# PSU200A_Ctrl.net
KiCad netlist of a schematic drawn in EAGLE
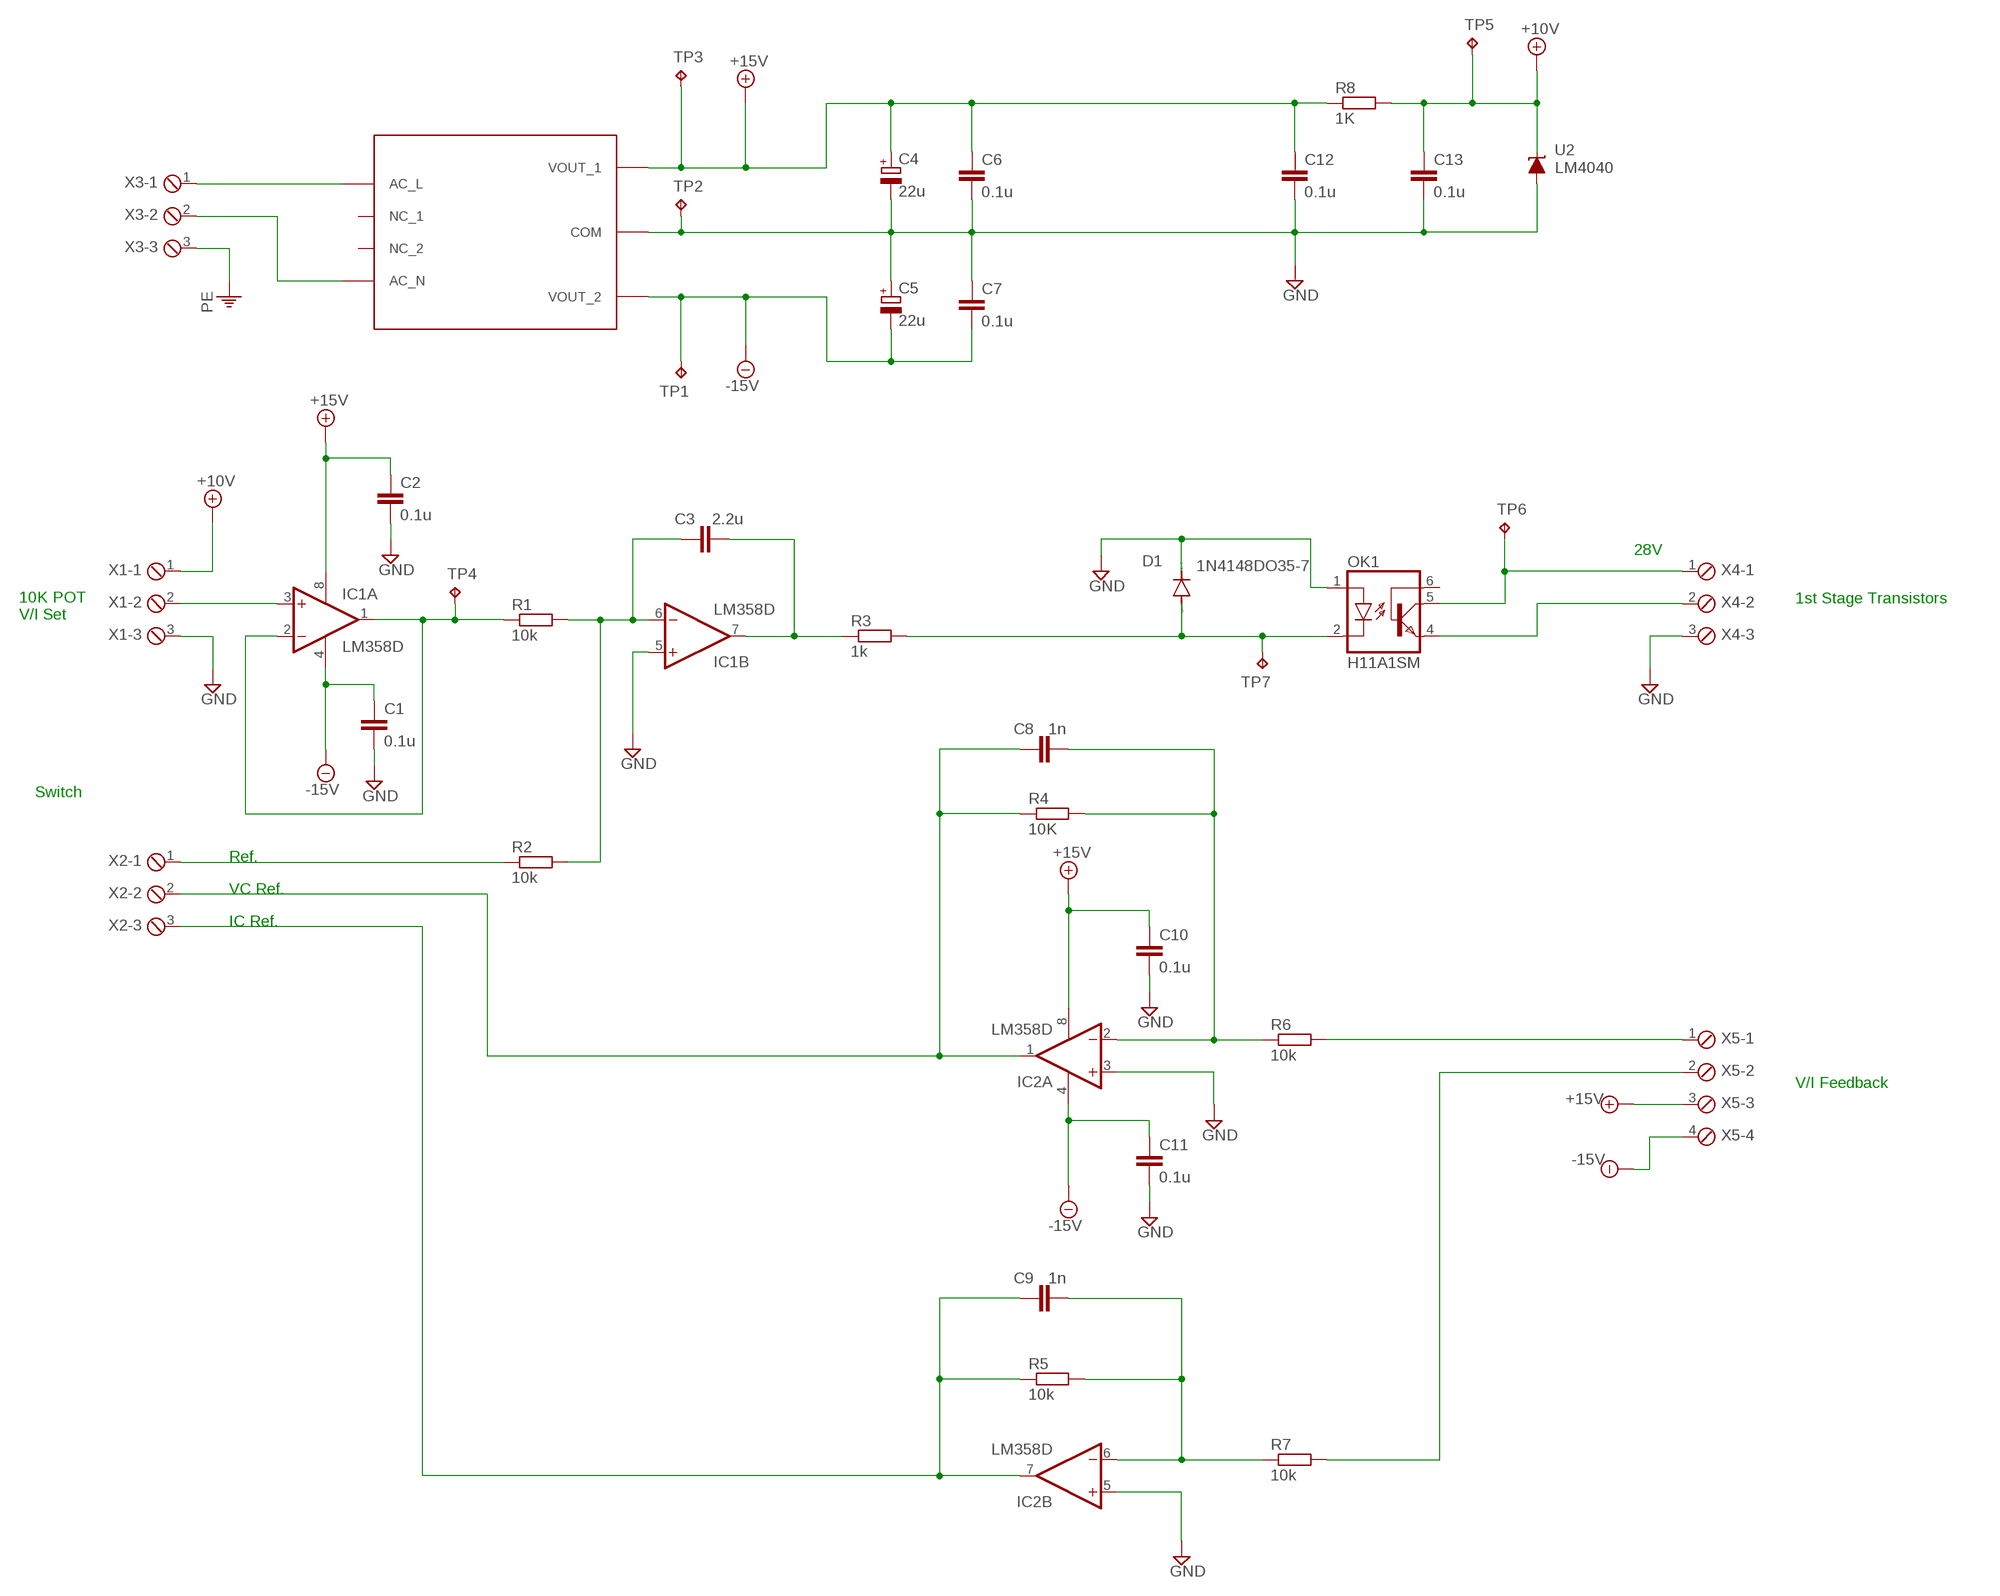
[diagram p0: schematic, sheet 1]

(export (version "E")
  (design (tool "Eeschema 10.0.6"))
  (components
    (comp (ref "C1")
      (value "0.1u")
      (footprint "eagle-import:C1206")
      (libsource (lib "eagle-import") (part "C-EUC1206"))
    )
    (comp (ref "C2")
      (value "0.1u")
      (footprint "eagle-import:C1206")
      (libsource (lib "eagle-import") (part "C-EUC1206"))
    )
    (comp (ref "C3")
      (value "2.2u")
      (footprint "eagle-import:C1206")
      (libsource (lib "eagle-import") (part "C-EUC1206"))
    )
    (comp (ref "C4")
      (value "22u")
      (footprint "eagle-import:PANASONIC_B")
      (libsource (lib "eagle-import") (part "CPOL-EUB"))
    )
    (comp (ref "C5")
      (value "22u")
      (footprint "eagle-import:PANASONIC_B")
      (libsource (lib "eagle-import") (part "CPOL-EUB"))
    )
    (comp (ref "C6")
      (value "0.1u")
      (footprint "eagle-import:C1206")
      (libsource (lib "eagle-import") (part "C-EUC1206"))
    )
    (comp (ref "C7")
      (value "0.1u")
      (footprint "eagle-import:C1206")
      (libsource (lib "eagle-import") (part "C-EUC1206"))
    )
    (comp (ref "C8")
      (value "1n")
      (footprint "eagle-import:C1206")
      (libsource (lib "eagle-import") (part "C-EUC1206"))
    )
    (comp (ref "C9")
      (value "1n")
      (footprint "eagle-import:C1206")
      (libsource (lib "eagle-import") (part "C-EUC1206"))
    )
    (comp (ref "C10")
      (value "0.1u")
      (footprint "eagle-import:C1206")
      (libsource (lib "eagle-import") (part "C-EUC1206"))
    )
    (comp (ref "C11")
      (value "0.1u")
      (footprint "eagle-import:C1206")
      (libsource (lib "eagle-import") (part "C-EUC1206"))
    )
    (comp (ref "C12")
      (value "0.1u")
      (footprint "eagle-import:C1206")
      (libsource (lib "eagle-import") (part "C-EUC1206"))
    )
    (comp (ref "C13")
      (value "0.1u")
      (footprint "eagle-import:C1206")
      (libsource (lib "eagle-import") (part "C-EUC1206"))
    )
    (comp (ref "D1")
      (value "1N4148DO35-7")
      (footprint "eagle-import:DO35-7")
      (libsource (lib "eagle-import") (part "1N4148DO35-7"))
    )
    (comp (ref "IC1")
      (value "LM358D")
      (footprint "eagle-import:SO08")
      (libsource (lib "eagle-import") (part "LM358D"))
    )
    (comp (ref "IC2")
      (value "LM358D")
      (footprint "eagle-import:SO08")
      (libsource (lib "eagle-import") (part "LM358D"))
    )
    (comp (ref "OK1")
      (value "H11A1SM")
      (footprint "eagle-import:DIL6-SMD")
      (libsource (lib "eagle-import") (part "H11A?MS1"))
    )
    (comp (ref "R1")
      (value "10k")
      (footprint "eagle-import:R1206")
      (libsource (lib "eagle-import") (part "R-EU_R1206"))
    )
    (comp (ref "R2")
      (value "10k")
      (footprint "eagle-import:R1206")
      (libsource (lib "eagle-import") (part "R-EU_R1206"))
    )
    (comp (ref "R3")
      (value "1k")
      (footprint "eagle-import:R1206")
      (libsource (lib "eagle-import") (part "R-EU_R1206"))
    )
    (comp (ref "R4")
      (value "10K")
      (footprint "eagle-import:R1206")
      (libsource (lib "eagle-import") (part "R-EU_R1206"))
    )
    (comp (ref "R5")
      (value "10k")
      (footprint "eagle-import:R1206")
      (libsource (lib "eagle-import") (part "R-EU_R1206"))
    )
    (comp (ref "R6")
      (value "10k")
      (footprint "eagle-import:R1206")
      (libsource (lib "eagle-import") (part "R-EU_R1206"))
    )
    (comp (ref "R7")
      (value "10k")
      (footprint "eagle-import:R1206")
      (libsource (lib "eagle-import") (part "R-EU_R1206"))
    )
    (comp (ref "R8")
      (value "1K")
      (footprint "eagle-import:R1210")
      (libsource (lib "eagle-import") (part "R-EU_R1210"))
    )
    (comp (ref "TP1")
      (value "TPPAD1-13")
      (footprint "eagle-import:P1-13")
      (libsource (lib "eagle-import") (part "TPPAD1-13"))
    )
    (comp (ref "TP2")
      (value "TPPAD1-13")
      (footprint "eagle-import:P1-13")
      (libsource (lib "eagle-import") (part "TPPAD1-13"))
    )
    (comp (ref "TP3")
      (value "TPPAD1-13")
      (footprint "eagle-import:P1-13")
      (libsource (lib "eagle-import") (part "TPPAD1-13"))
    )
    (comp (ref "TP4")
      (value "TPPAD1-13")
      (footprint "eagle-import:P1-13")
      (libsource (lib "eagle-import") (part "TPPAD1-13"))
    )
    (comp (ref "TP5")
      (value "TPPAD1-13")
      (footprint "eagle-import:P1-13")
      (libsource (lib "eagle-import") (part "TPPAD1-13"))
    )
    (comp (ref "TP6")
      (value "TPPAD1-13")
      (footprint "eagle-import:P1-13")
      (libsource (lib "eagle-import") (part "TPPAD1-13"))
    )
    (comp (ref "TP7")
      (value "TPPAD1-13")
      (footprint "eagle-import:P1-13")
      (libsource (lib "eagle-import") (part "TPPAD1-13"))
    )
    (comp (ref "U1")
      (value "TMPM04215")
      (footprint "eagle-import:TMPM04XXX")
      (libsource (lib "eagle-import") (part "TMPM04215"))
    )
    (comp (ref "U2")
      (value "LM4040")
      (footprint "eagle-import:TO92-")
      (libsource (lib "eagle-import") (part "LM4040"))
    )
    (comp (ref "X1")
      (value "MPT3")
      (footprint "eagle-import:3POL254")
      (libsource (lib "eagle-import") (part "MPT3"))
    )
    (comp (ref "X2")
      (value "MPT3")
      (footprint "eagle-import:3POL254")
      (libsource (lib "eagle-import") (part "MPT3"))
    )
    (comp (ref "X3")
      (value "MPT3")
      (footprint "eagle-import:3POL254")
      (libsource (lib "eagle-import") (part "MPT3"))
    )
    (comp (ref "X4")
      (value "MPT3")
      (footprint "eagle-import:3POL254")
      (libsource (lib "eagle-import") (part "MPT3"))
    )
    (comp (ref "X5")
      (value "MPT4")
      (footprint "eagle-import:4POL254")
      (libsource (lib "eagle-import") (part "MPT4"))
    )
  )
  (nets
    (net (code "1") (name "+10V") (class "Default")
      (node (ref "C13") (pin "1") (pinfunction "1_1") (pintype "passive"))
      (node (ref "R8") (pin "2") (pinfunction "2_2") (pintype "passive"))
      (node (ref "TP5") (pin "TP") (pinfunction "TP_TP") (pintype "input"))
      (node (ref "U2") (pin "2") (pinfunction "C_2") (pintype "passive"))
      (node (ref "X1") (pin "1") (pinfunction "1_1") (pintype "passive"))
    )
    (net (code "2") (name "+15V") (class "Default")
      (node (ref "C10") (pin "1") (pinfunction "1_1") (pintype "passive"))
      (node (ref "C12") (pin "1") (pinfunction "1_1") (pintype "passive"))
      (node (ref "C2") (pin "1") (pinfunction "1_1") (pintype "passive"))
      (node (ref "C4") (pin "+") (pinfunction "+_+") (pintype "passive"))
      (node (ref "C6") (pin "1") (pinfunction "1_1") (pintype "passive"))
      (node (ref "IC1") (pin "8") (pinfunction "V+_8") (pintype "power_in"))
      (node (ref "IC2") (pin "8") (pinfunction "V+_8") (pintype "power_in"))
      (node (ref "R8") (pin "1") (pinfunction "1_1") (pintype "passive"))
      (node (ref "TP3") (pin "TP") (pinfunction "TP_TP") (pintype "input"))
      (node (ref "U1") (pin "P$3") (pinfunction "VOUT_1_P$3") (pintype "bidirectional"))
      (node (ref "X5") (pin "3") (pinfunction "1_3") (pintype "passive"))
    )
    (net (code "3") (name "-15V") (class "Default")
      (node (ref "C1") (pin "1") (pinfunction "1_1") (pintype "passive"))
      (node (ref "C11") (pin "1") (pinfunction "1_1") (pintype "passive"))
      (node (ref "C5") (pin "-") (pinfunction "-_-") (pintype "passive"))
      (node (ref "C7") (pin "2") (pinfunction "2_2") (pintype "passive"))
      (node (ref "IC1") (pin "4") (pinfunction "V-_4") (pintype "power_in"))
      (node (ref "IC2") (pin "4") (pinfunction "V-_4") (pintype "power_in"))
      (node (ref "TP1") (pin "TP") (pinfunction "TP_TP") (pintype "input"))
      (node (ref "U1") (pin "P$5") (pinfunction "VOUT_2_P$5") (pintype "bidirectional"))
      (node (ref "X5") (pin "4") (pinfunction "1_4") (pintype "passive"))
    )
    (net (code "4") (name "GND") (class "Default")
      (node (ref "C1") (pin "2") (pinfunction "2_2") (pintype "passive"))
      (node (ref "C10") (pin "2") (pinfunction "2_2") (pintype "passive"))
      (node (ref "C11") (pin "2") (pinfunction "2_2") (pintype "passive"))
      (node (ref "C12") (pin "2") (pinfunction "2_2") (pintype "passive"))
      (node (ref "C13") (pin "2") (pinfunction "2_2") (pintype "passive"))
      (node (ref "C2") (pin "2") (pinfunction "2_2") (pintype "passive"))
      (node (ref "C4") (pin "-") (pinfunction "-_-") (pintype "passive"))
      (node (ref "C5") (pin "+") (pinfunction "+_+") (pintype "passive"))
      (node (ref "C6") (pin "2") (pinfunction "2_2") (pintype "passive"))
      (node (ref "C7") (pin "1") (pinfunction "1_1") (pintype "passive"))
      (node (ref "D1") (pin "C") (pinfunction "C_C") (pintype "passive"))
      (node (ref "IC1") (pin "5") (pinfunction "+IN_5") (pintype "input"))
      (node (ref "IC2") (pin "3") (pinfunction "+IN_3") (pintype "input"))
      (node (ref "IC2") (pin "5") (pinfunction "+IN_5") (pintype "input"))
      (node (ref "OK1") (pin "1") (pinfunction "A_1") (pintype "passive"))
      (node (ref "TP2") (pin "TP") (pinfunction "TP_TP") (pintype "input"))
      (node (ref "U1") (pin "P$4") (pinfunction "COM_P$4") (pintype "bidirectional"))
      (node (ref "U2") (pin "3") (pinfunction "A_3") (pintype "passive"))
      (node (ref "X1") (pin "3") (pinfunction "1_3") (pintype "passive"))
      (node (ref "X4") (pin "3") (pinfunction "1_3") (pintype "passive"))
    )
    (net (code "5") (name "Net-(IC1A-+IN)") (class "Default")
      (node (ref "IC1") (pin "3") (pinfunction "+IN_3") (pintype "input"))
      (node (ref "X1") (pin "2") (pinfunction "1_2") (pintype "passive"))
    )
    (net (code "6") (name "Net-(IC1A--IN)") (class "Default")
      (node (ref "IC1") (pin "1") (pinfunction "OUT_1") (pintype "output"))
      (node (ref "IC1") (pin "2") (pinfunction "-IN_2") (pintype "input"))
      (node (ref "R1") (pin "1") (pinfunction "1_1") (pintype "passive"))
      (node (ref "TP4") (pin "TP") (pinfunction "TP_TP") (pintype "input"))
    )
    (net (code "7") (name "Net-(IC1B--IN)") (class "Default")
      (node (ref "C3") (pin "1") (pinfunction "1_1") (pintype "passive"))
      (node (ref "IC1") (pin "6") (pinfunction "-IN_6") (pintype "input"))
      (node (ref "R1") (pin "2") (pinfunction "2_2") (pintype "passive"))
      (node (ref "R2") (pin "2") (pinfunction "2_2") (pintype "passive"))
    )
    (net (code "8") (name "Net-(IC1B-OUT)") (class "Default")
      (node (ref "C3") (pin "2") (pinfunction "2_2") (pintype "passive"))
      (node (ref "IC1") (pin "7") (pinfunction "OUT_7") (pintype "output"))
      (node (ref "R3") (pin "1") (pinfunction "1_1") (pintype "passive"))
    )
    (net (code "9") (name "Net-(IC2A--IN)") (class "Default")
      (node (ref "C8") (pin "2") (pinfunction "2_2") (pintype "passive"))
      (node (ref "IC2") (pin "2") (pinfunction "-IN_2") (pintype "input"))
      (node (ref "R4") (pin "2") (pinfunction "2_2") (pintype "passive"))
      (node (ref "R6") (pin "1") (pinfunction "1_1") (pintype "passive"))
    )
    (net (code "10") (name "Net-(IC2A-OUT)") (class "Default")
      (node (ref "C8") (pin "1") (pinfunction "1_1") (pintype "passive"))
      (node (ref "IC2") (pin "1") (pinfunction "OUT_1") (pintype "output"))
      (node (ref "R4") (pin "1") (pinfunction "1_1") (pintype "passive"))
      (node (ref "X2") (pin "2") (pinfunction "1_2") (pintype "passive"))
    )
    (net (code "11") (name "Net-(IC2B--IN)") (class "Default")
      (node (ref "C9") (pin "2") (pinfunction "2_2") (pintype "passive"))
      (node (ref "IC2") (pin "6") (pinfunction "-IN_6") (pintype "input"))
      (node (ref "R5") (pin "2") (pinfunction "2_2") (pintype "passive"))
      (node (ref "R7") (pin "1") (pinfunction "1_1") (pintype "passive"))
    )
    (net (code "12") (name "Net-(IC2B-OUT)") (class "Default")
      (node (ref "C9") (pin "1") (pinfunction "1_1") (pintype "passive"))
      (node (ref "IC2") (pin "7") (pinfunction "OUT_7") (pintype "output"))
      (node (ref "R5") (pin "1") (pinfunction "1_1") (pintype "passive"))
      (node (ref "X2") (pin "3") (pinfunction "1_3") (pintype "passive"))
    )
    (net (code "13") (name "Net-(OK1-C)") (class "Default")
      (node (ref "D1") (pin "A") (pinfunction "A_A") (pintype "passive"))
      (node (ref "OK1") (pin "2") (pinfunction "C_2") (pintype "passive"))
      (node (ref "R3") (pin "2") (pinfunction "2_2") (pintype "passive"))
      (node (ref "TP7") (pin "TP") (pinfunction "TP_TP") (pintype "input"))
    )
    (net (code "14") (name "Net-(OK1-COL)") (class "Default")
      (node (ref "OK1") (pin "5") (pinfunction "COL_5") (pintype "passive"))
      (node (ref "TP6") (pin "TP") (pinfunction "TP_TP") (pintype "input"))
      (node (ref "X4") (pin "1") (pinfunction "1_1") (pintype "passive"))
    )
    (net (code "15") (name "Net-(OK1-EMI)") (class "Default")
      (node (ref "OK1") (pin "4") (pinfunction "EMI_4") (pintype "passive"))
      (node (ref "X4") (pin "2") (pinfunction "1_2") (pintype "passive"))
    )
    (net (code "16") (name "Net-(R2-Pad1)") (class "Default")
      (node (ref "R2") (pin "1") (pinfunction "1_1") (pintype "passive"))
      (node (ref "X2") (pin "1") (pinfunction "1_1") (pintype "passive"))
    )
    (net (code "17") (name "Net-(R6-Pad2)") (class "Default")
      (node (ref "R6") (pin "2") (pinfunction "2_2") (pintype "passive"))
      (node (ref "X5") (pin "1") (pinfunction "1_1") (pintype "passive"))
    )
    (net (code "18") (name "Net-(U1-AC_L)") (class "Default")
      (node (ref "U1") (pin "P$7") (pinfunction "AC_L_P$7") (pintype "bidirectional"))
      (node (ref "X3") (pin "1") (pinfunction "1_1") (pintype "passive"))
    )
    (net (code "19") (name "Net-(U1-AC_N)") (class "Default")
      (node (ref "U1") (pin "P$6") (pinfunction "AC_N_P$6") (pintype "bidirectional"))
      (node (ref "X3") (pin "2") (pinfunction "1_2") (pintype "passive"))
    )
    (net (code "20") (name "Net-(X5B-1)") (class "Default")
      (node (ref "R7") (pin "2") (pinfunction "2_2") (pintype "passive"))
      (node (ref "X5") (pin "2") (pinfunction "1_2") (pintype "passive"))
    )
    (net (code "21") (name "PE") (class "Default")
      (node (ref "X3") (pin "3") (pinfunction "1_3") (pintype "passive"))
    )
    (net (code "22") (name "unconnected-(OK1-BAS-Pad6)") (class "Default")
      (node (ref "OK1") (pin "6") (pinfunction "BAS_6") (pintype "passive"))
    )
    (net (code "23") (name "unconnected-(U1-NC_1-PadP$1)") (class "Default")
      (node (ref "U1") (pin "P$1") (pinfunction "NC_1_P$1") (pintype "no_connect"))
    )
    (net (code "24") (name "unconnected-(U1-NC_2-PadP$2)") (class "Default")
      (node (ref "U1") (pin "P$2") (pinfunction "NC_2_P$2") (pintype "no_connect"))
    )
  )
)
